# 3V3_Digital_Out.net
KiCad netlist of a schematic drawn in Altium Designer
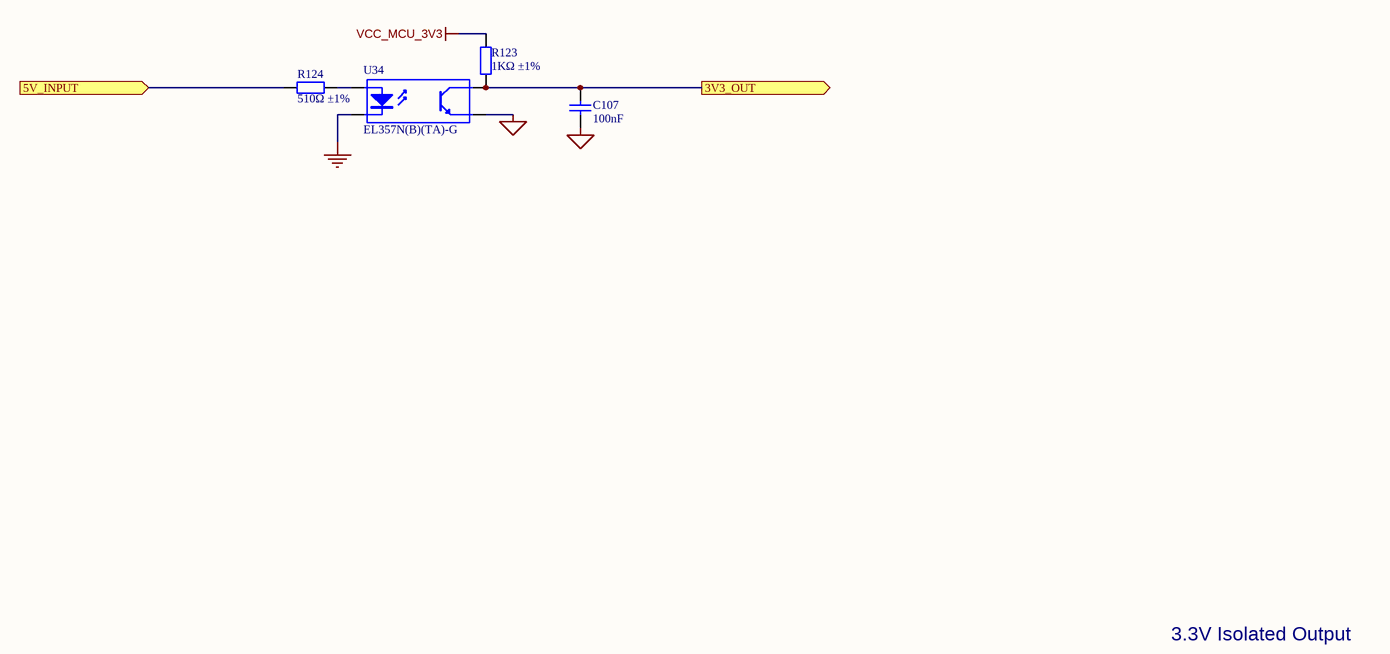
[diagram p0: 3V3_Digital_Out.SchDoc]

(export (version "E")
  (design (tool "Eeschema 10.0.6"))
  (components
    (comp (ref "C107")
      (value "100nF")
      (footprint "0402_C")
      (description "16V 100nF X7R ±10% 0402 Multilayer Ceramic Capacitors MLCC - SMD/SMT ROHS")
      (fields (field (name "MANUFACTURER") "Samsung Electro-Mechanics") (field (name "TOLERANCE") "10%"))
      (libsource (lib "Sienci_Labs") (part "0402 100nF (104) 10% 16V"))
    )
    (comp (ref "R123")
      (value "1KΩ ±1%")
      (footprint "0402_R")
      (description "Chip resistor")
      (fields
        (field (name "MANUFACTURER") "Uniroyal Elec")
        (field (name "MANUFACTURER PART NUMBER") "0402WGF1001TCE")
      )
      (libsource (lib "RES") (part "0402 1K (1001) 1%"))
    )
    (comp (ref "R124")
      (value "510Ω ±1%")
      (footprint "0402_R")
      (description "Chip resistor")
      (fields
        (field (name "MANUFACTURER") "Uniroyal Elec")
        (field (name "MANUFACTURER PART NUMBER") "0402WGF5100TCE")
      )
      (libsource (lib "RES") (part "0402 510R (5100) 1%"))
    )
    (comp (ref "U34")
      (value "EL357N(B)(TA)-G")
      (footprint "Miscellaneous Devices LC:SOP-4_P2.54")
      (description "Optocoupler SOP-4, EL357N(B)(TA)-G, Everlight Electronics")
      (fields (field (name "MANUFACTURER") "Everlight"))
      (libsource (lib "Sienci_Labs") (part "EL357N(B)(TA)-G_[C6649]"))
    )
  )
  (nets
    (net (code "1") (name "/3V3_OUT") (class "Default")
      (node (ref "C107") (pin "2") (pinfunction "2_2") (pintype "passive"))
      (node (ref "R123") (pin "2") (pinfunction "2_2") (pintype "passive"))
      (node (ref "U34") (pin "4") (pinfunction "C_4") (pintype "passive"))
    )
    (net (code "2") (name "/5V_INPUT") (class "Default")
      (node (ref "R124") (pin "1") (pinfunction "1_1") (pintype "passive"))
    )
    (net (code "3") (name "GND") (class "Default")
      (node (ref "U34") (pin "2") (pinfunction "K_2") (pintype "passive"))
    )
    (net (code "4") (name "MCU_GND") (class "Default")
      (node (ref "C107") (pin "1") (pinfunction "1_1") (pintype "passive"))
      (node (ref "U34") (pin "3") (pinfunction "E_3") (pintype "passive"))
    )
    (net (code "5") (name "Net-(U34-A)") (class "Default")
      (node (ref "R124") (pin "2") (pinfunction "2_2") (pintype "passive"))
      (node (ref "U34") (pin "1") (pinfunction "A_1") (pintype "passive"))
    )
    (net (code "6") (name "VCC_MCU_3V3") (class "Default")
      (node (ref "R123") (pin "1") (pinfunction "1_1") (pintype "passive"))
    )
  )
)
